# PWR_CTRL.net
KiCad netlist of a schematic drawn in Altium Designer
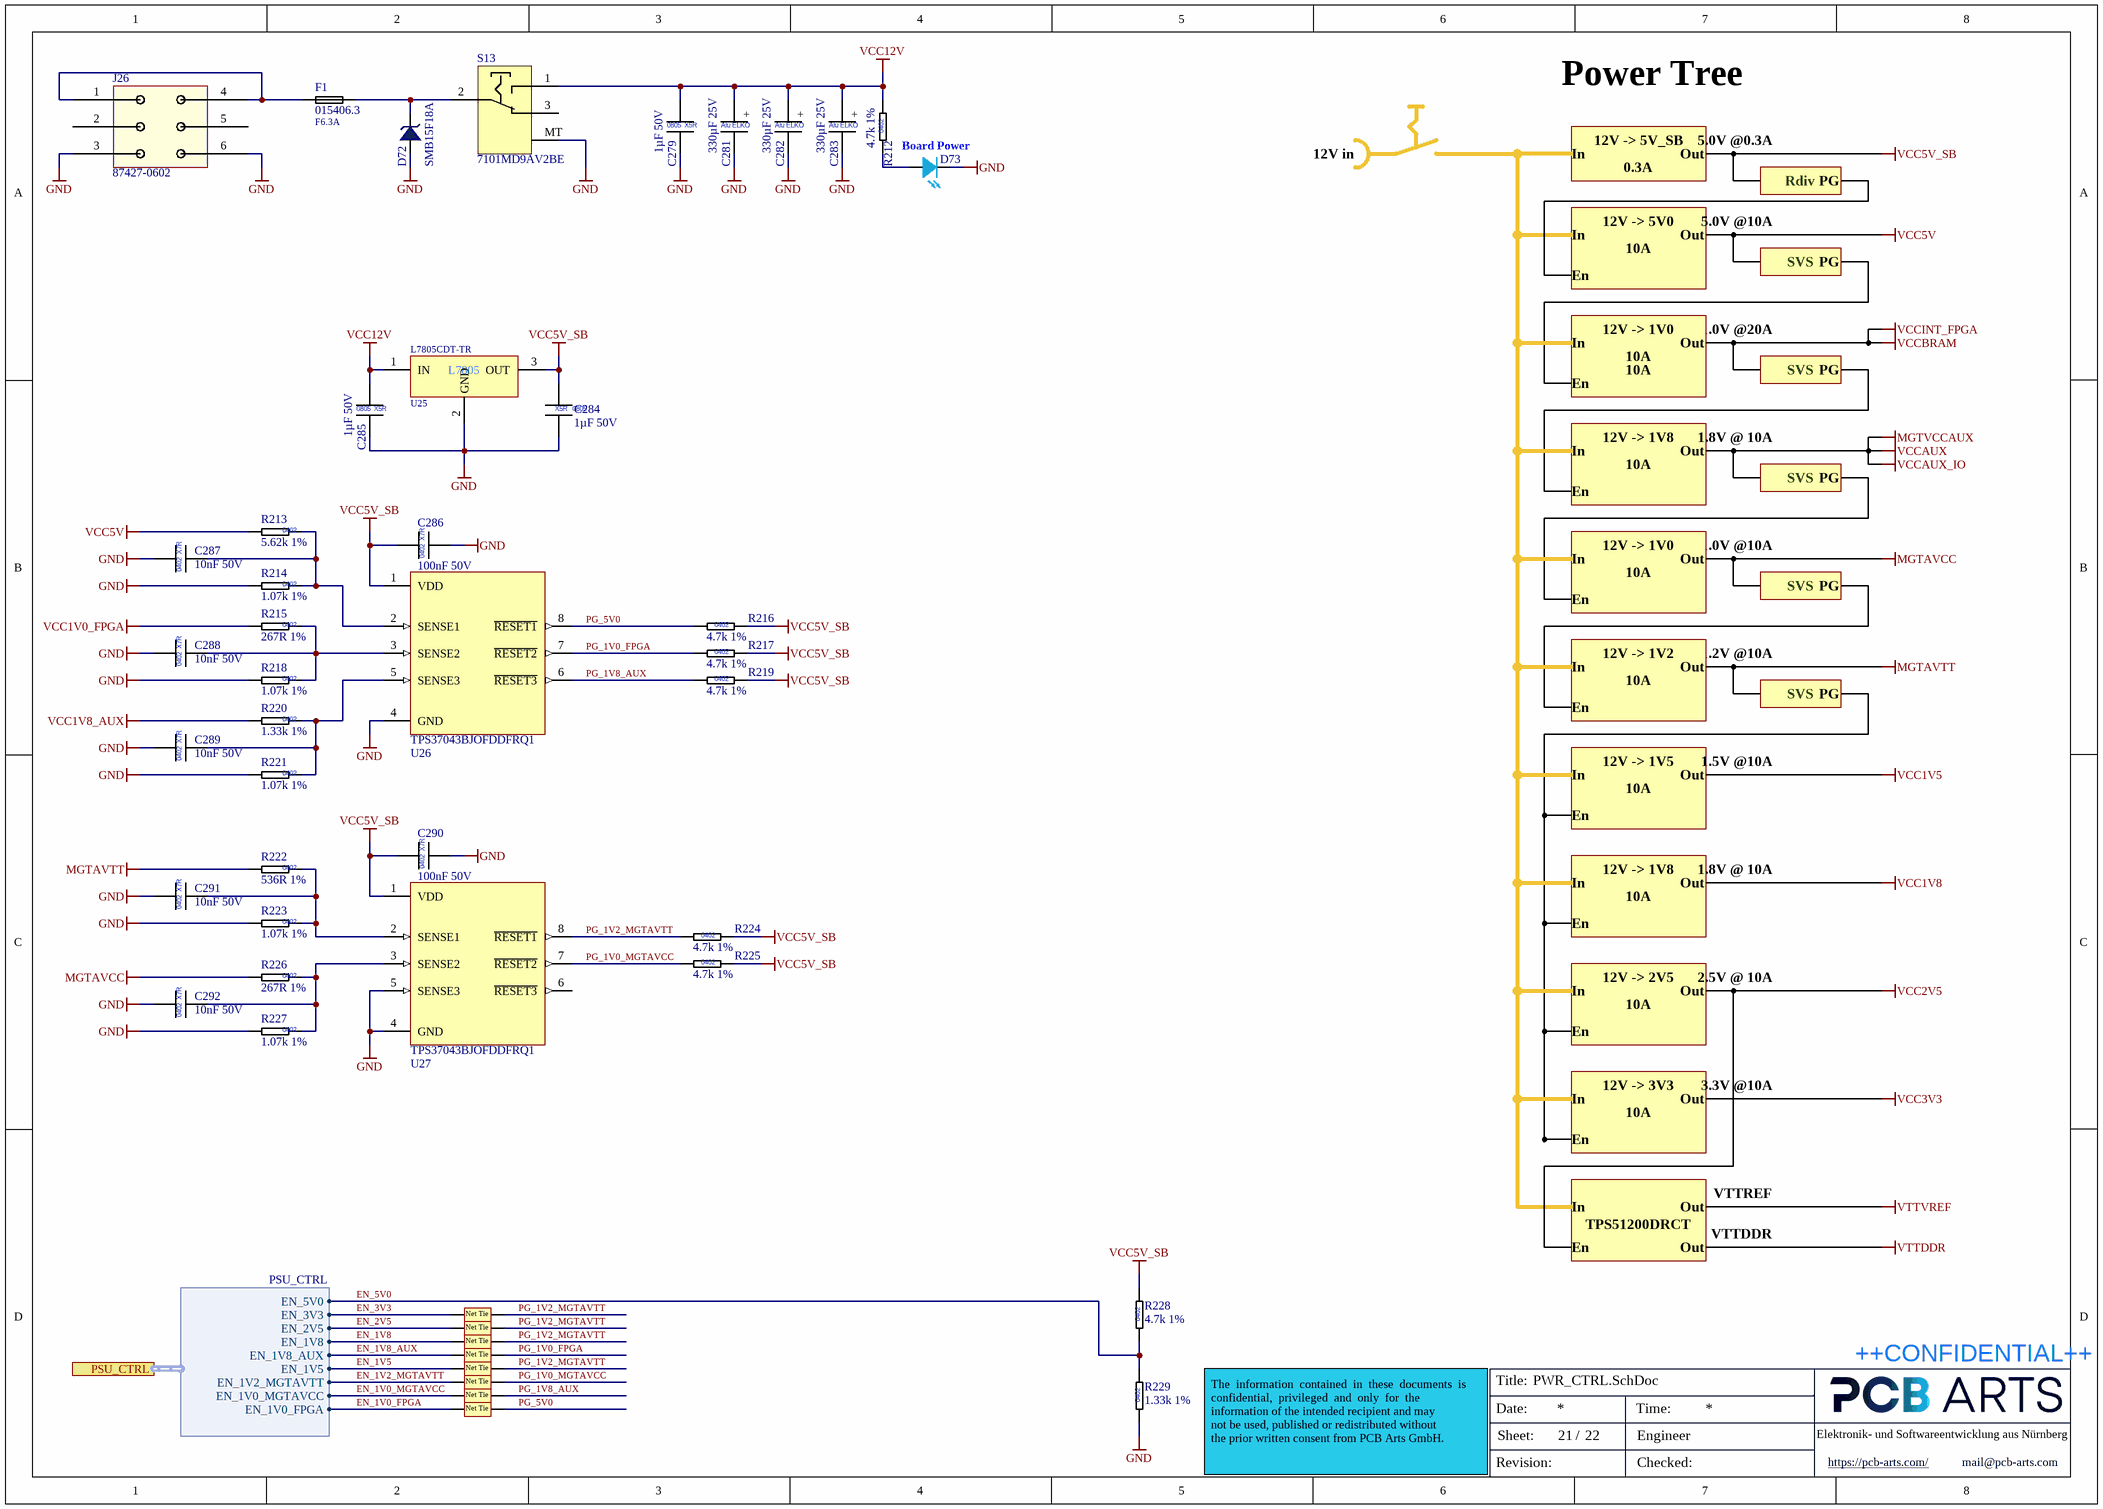
[diagram p0: PWR_CTRL.SchDoc]

(export (version "E")
  (design (tool "Eeschema 10.0.6"))
  (components
    (comp (ref "C279")
      (value "1µF 50V")
      (footprint "Cap:CAP_0805")
      (description "Multilayer Ceramic Capacitors MLCC - SMD/SMT 0805 50VDC")
      (libsource (lib "Cap") (part "CAP_0805_1µF_50V"))
    )
    (comp (ref "C281")
      (value "330µF 25V")
      (footprint "Cap:WCAP-PTG5_D10H12.5")
      (description "Organische Polymer-Aluminiumkondensatoren 330uF 25 Volts 20% AEC-Q200")
      (libsource (lib "Cap") (part "CAP_D10L12.5_330µF_25V"))
    )
    (comp (ref "C282")
      (value "330µF 25V")
      (footprint "Cap:WCAP-PTG5_D10H12.5")
      (description "Organische Polymer-Aluminiumkondensatoren 330uF 25 Volts 20% AEC-Q200")
      (libsource (lib "Cap") (part "CAP_D10L12.5_330µF_25V"))
    )
    (comp (ref "C283")
      (value "330µF 25V")
      (footprint "Cap:WCAP-PTG5_D10H12.5")
      (description "Organische Polymer-Aluminiumkondensatoren 330uF 25 Volts 20% AEC-Q200")
      (libsource (lib "Cap") (part "CAP_D10L12.5_330µF_25V"))
    )
    (comp (ref "C284")
      (value "1µF 50V")
      (footprint "Cap:CAP_0805")
      (description "Multilayer Ceramic Capacitors MLCC - SMD/SMT 0805 50VDC")
      (libsource (lib "Cap") (part "CAP_0805_1µF_50V"))
    )
    (comp (ref "C285")
      (value "1µF 50V")
      (footprint "Cap:CAP_0805")
      (description "Multilayer Ceramic Capacitors MLCC - SMD/SMT 0805 50VDC")
      (libsource (lib "Cap") (part "CAP_0805_1µF_50V"))
    )
    (comp (ref "C286")
      (value "100nF 50V")
      (footprint "Cap:CAP_0402_L")
      (description "Multilayer Ceramic Capacitors MLCC - SMD/SMT 0402 50VDC")
      (libsource (lib "Cap") (part "CAP_0402_100nF_50V"))
    )
    (comp (ref "C287")
      (value "10nF 50V")
      (footprint "Cap:CAP_0402_L")
      (description "Multilayer Ceramic Capacitors MLCC - SMD/SMT 0402 50VDC")
      (libsource (lib "Cap") (part "CAP_0402_10nF_50V"))
    )
    (comp (ref "C288")
      (value "10nF 50V")
      (footprint "Cap:CAP_0402_L")
      (description "Multilayer Ceramic Capacitors MLCC - SMD/SMT 0402 50VDC")
      (libsource (lib "Cap") (part "CAP_0402_10nF_50V"))
    )
    (comp (ref "C289")
      (value "10nF 50V")
      (footprint "Cap:CAP_0402_L")
      (description "Multilayer Ceramic Capacitors MLCC - SMD/SMT 0402 50VDC")
      (libsource (lib "Cap") (part "CAP_0402_10nF_50V"))
    )
    (comp (ref "C290")
      (value "100nF 50V")
      (footprint "Cap:CAP_0402_L")
      (description "Multilayer Ceramic Capacitors MLCC - SMD/SMT 0402 50VDC")
      (libsource (lib "Cap") (part "CAP_0402_100nF_50V"))
    )
    (comp (ref "C291")
      (value "10nF 50V")
      (footprint "Cap:CAP_0402_L")
      (description "Multilayer Ceramic Capacitors MLCC - SMD/SMT 0402 50VDC")
      (libsource (lib "Cap") (part "CAP_0402_10nF_50V"))
    )
    (comp (ref "C292")
      (value "10nF 50V")
      (footprint "Cap:CAP_0402_L")
      (description "Multilayer Ceramic Capacitors MLCC - SMD/SMT 0402 50VDC")
      (libsource (lib "Cap") (part "CAP_0402_10nF_50V"))
    )
    (comp (ref "D72")
      (value "SMB15F18A")
      (footprint "Protec:DO221-AA")
      (description "ESD-Entstörer/TVS-Dioden 1500 W, 18 V TVS")
      (libsource (lib "Protec") (part "SMB15F18A_ESD-Entstörer/TVS-Dioden 1500 W, 18 V TVS"))
    )
    (comp (ref "D73")
      (value "LTST-S270TBKT")
      (footprint "Active:LED-0603 Sideview")
      (description "BLUE  0603 Light Emitting Diode")
      (libsource (lib "Active") (part "LED 0603 Blue Sideview"))
    )
    (comp (ref "F1")
      (value "015406.3")
      (footprint "Passive:154 Series Littelfuse")
      (description "SMD Ceramic Holder with Fuse - Fast 6.3A")
      (fields (field (name "CURRENT") "F6.3A"))
      (libsource (lib "Passive") (part "015406.3_SMD Ceramic Holder with Fuse - Fast 6.3A"))
    )
    (comp (ref "J26")
      (value "87427-0602")
      (footprint "Molex 87427-0602")
      (description "Mini-Fit Jr. Right angle Header, 4.20mm Pitch, Dual Row, 6 Circuits")
      (libsource (lib "Conn") (part "87427-0602_Mini-Fit Jr. Right angle Header, 4.20mm Pitch, Dual Row, 6 Circuits"))
    )
    (comp (ref "NT1")
      (value "Net Tie")
      (footprint "Passive:Net Tie-0.3")
      (libsource (lib "Passive") (part "Net Tie"))
    )
    (comp (ref "NT2")
      (value "Net Tie")
      (footprint "Passive:Net Tie-0.3")
      (libsource (lib "Passive") (part "Net Tie"))
    )
    (comp (ref "NT3")
      (value "Net Tie")
      (footprint "Passive:Net Tie-0.3")
      (libsource (lib "Passive") (part "Net Tie"))
    )
    (comp (ref "NT4")
      (value "Net Tie")
      (footprint "Passive:Net Tie-0.3")
      (libsource (lib "Passive") (part "Net Tie"))
    )
    (comp (ref "NT5")
      (value "Net Tie")
      (footprint "Passive:Net Tie-0.3")
      (libsource (lib "Passive") (part "Net Tie"))
    )
    (comp (ref "NT6")
      (value "Net Tie")
      (footprint "Passive:Net Tie-0.3")
      (libsource (lib "Passive") (part "Net Tie"))
    )
    (comp (ref "NT7")
      (value "Net Tie")
      (footprint "Passive:Net Tie-0.3")
      (libsource (lib "Passive") (part "Net Tie"))
    )
    (comp (ref "NT8")
      (value "Net Tie")
      (footprint "Passive:Net Tie-0.3")
      (libsource (lib "Passive") (part "Net Tie"))
    )
    (comp (ref "R212")
      (value "4.7k 1%")
      (footprint "Res:RES_0402_L")
      (description "Thick Film Resistors - SMD 4.7kOhm 1%")
      (libsource (lib "Res") (part "RES_0402_4.7k_1%"))
    )
    (comp (ref "R213")
      (value "5.62k 1%")
      (footprint "Res:RES_0402_L")
      (description "Thick Film Resistors - SMD 5.62kOhm 1%")
      (libsource (lib "Res") (part "RES_0402_5.62k_1%"))
    )
    (comp (ref "R214")
      (value "1.07k 1%")
      (footprint "Res:RES_0402_L")
      (description "Thick Film Resistors - SMD 1.07kOhm 1%")
      (libsource (lib "Res") (part "RES_0402_1.07k_1%"))
    )
    (comp (ref "R215")
      (value "267R 1%")
      (footprint "Res:RES_0402_L")
      (description "Thick Film Resistors - SMD 267Ohm 1%")
      (libsource (lib "Res") (part "RES_0402_267R_1%"))
    )
    (comp (ref "R216")
      (value "4.7k 1%")
      (footprint "Res:RES_0402_L")
      (description "Thick Film Resistors - SMD 4.7kOhm 1%")
      (libsource (lib "Res") (part "RES_0402_4.7k_1%"))
    )
    (comp (ref "R217")
      (value "4.7k 1%")
      (footprint "Res:RES_0402_L")
      (description "Thick Film Resistors - SMD 4.7kOhm 1%")
      (libsource (lib "Res") (part "RES_0402_4.7k_1%"))
    )
    (comp (ref "R218")
      (value "1.07k 1%")
      (footprint "Res:RES_0402_L")
      (description "Thick Film Resistors - SMD 1.07kOhm 1%")
      (libsource (lib "Res") (part "RES_0402_1.07k_1%"))
    )
    (comp (ref "R219")
      (value "4.7k 1%")
      (footprint "Res:RES_0402_L")
      (description "Thick Film Resistors - SMD 4.7kOhm 1%")
      (libsource (lib "Res") (part "RES_0402_4.7k_1%"))
    )
    (comp (ref "R220")
      (value "1.33k 1%")
      (footprint "Res:RES_0402_L")
      (description "Thick Film Resistors - SMD 1.33kOhm 1%")
      (libsource (lib "Res") (part "RES_0402_1.33k_1%"))
    )
    (comp (ref "R221")
      (value "1.07k 1%")
      (footprint "Res:RES_0402_L")
      (description "Thick Film Resistors - SMD 1.07kOhm 1%")
      (libsource (lib "Res") (part "RES_0402_1.07k_1%"))
    )
    (comp (ref "R222")
      (value "536R 1%")
      (footprint "Res:RES_0402_L")
      (description "Thick Film Resistors - SMD 536Ohm 1%")
      (libsource (lib "Res") (part "RES_0402_536R_1%"))
    )
    (comp (ref "R223")
      (value "1.07k 1%")
      (footprint "Res:RES_0402_L")
      (description "Thick Film Resistors - SMD 1.07kOhm 1%")
      (libsource (lib "Res") (part "RES_0402_1.07k_1%"))
    )
    (comp (ref "R224")
      (value "4.7k 1%")
      (footprint "Res:RES_0402_L")
      (description "Thick Film Resistors - SMD 4.7kOhm 1%")
      (libsource (lib "Res") (part "RES_0402_4.7k_1%"))
    )
    (comp (ref "R225")
      (value "4.7k 1%")
      (footprint "Res:RES_0402_L")
      (description "Thick Film Resistors - SMD 4.7kOhm 1%")
      (libsource (lib "Res") (part "RES_0402_4.7k_1%"))
    )
    (comp (ref "R226")
      (value "267R 1%")
      (footprint "Res:RES_0402_L")
      (description "Thick Film Resistors - SMD 267Ohm 1%")
      (libsource (lib "Res") (part "RES_0402_267R_1%"))
    )
    (comp (ref "R227")
      (value "1.07k 1%")
      (footprint "Res:RES_0402_L")
      (description "Thick Film Resistors - SMD 1.07kOhm 1%")
      (libsource (lib "Res") (part "RES_0402_1.07k_1%"))
    )
    (comp (ref "R228")
      (value "4.7k 1%")
      (footprint "Res:RES_0402_L")
      (description "Thick Film Resistors - SMD 4.7kOhm 1%")
      (libsource (lib "Res") (part "RES_0402_4.7k_1%"))
    )
    (comp (ref "R229")
      (value "1.33k 1%")
      (footprint "Res:RES_0402_L")
      (description "Thick Film Resistors - SMD 1.33kOhm 1%")
      (libsource (lib "Res") (part "RES_0402_1.33k_1%"))
    )
    (comp (ref "S13")
      (value "7101MD9AV2BE")
      (footprint "Electro_Mech:7101MD9AV2BE")
      (description "Kippschalter SPDT Right Angle Vertical")
      (libsource (lib "Electro_Mech") (part "7101MD9AV2BE_Kippschalter SPDT Right Angle Vertical"))
    )
    (comp (ref "U25")
      (value "L7805CDT-TR")
      (footprint "Power:DPAK230P991X241-3N")
      (description "Linear Voltage Regulators 5.0V 1.0A Positive")
      (libsource (lib "Power") (part "L7805CDT-TR_Linear Voltage Regulators 5.0V 1.0A"))
    )
    (comp (ref "U26")
      (value "TPS37043BJOFDDFRQ1")
      (footprint "Comp:SOT65P295X160-8N")
      (description "Triple Supply Voltage Window Supervisors With Fixed Delay, Open Drain Output")
      (libsource (lib "Comp") (part "TPS37043BJOFDDFRQ1_Triple Supply Voltage Window Supervisors"))
    )
    (comp (ref "U27")
      (value "TPS37043BJOFDDFRQ1")
      (footprint "Comp:SOT65P295X160-8N")
      (description "Triple Supply Voltage Window Supervisors With Fixed Delay, Open Drain Output")
      (libsource (lib "Comp") (part "TPS37043BJOFDDFRQ1_Triple Supply Voltage Window Supervisors"))
    )
  )
  (nets
    (net (code "2") (name "/EN_1V0_FPGA") (class "Default")
      (node (ref "NT8") (pin "1") (pinfunction "1_1") (pintype "passive"))
    )
    (net (code "3") (name "/EN_1V0_MGTAVCC") (class "Default")
      (node (ref "NT7") (pin "1") (pinfunction "1_1") (pintype "passive"))
    )
    (net (code "4") (name "/EN_1V2_MGTAVTT") (class "Default")
      (node (ref "NT6") (pin "1") (pinfunction "1_1") (pintype "passive"))
    )
    (net (code "5") (name "/EN_1V5") (class "Default")
      (node (ref "NT5") (pin "1") (pinfunction "1_1") (pintype "passive"))
    )
    (net (code "6") (name "/EN_1V8") (class "Default")
      (node (ref "NT3") (pin "1") (pinfunction "1_1") (pintype "passive"))
    )
    (net (code "7") (name "/EN_1V8_AUX") (class "Default")
      (node (ref "NT4") (pin "1") (pinfunction "1_1") (pintype "passive"))
    )
    (net (code "8") (name "/EN_2V5") (class "Default")
      (node (ref "NT2") (pin "1") (pinfunction "1_1") (pintype "passive"))
    )
    (net (code "9") (name "/EN_3V3") (class "Default")
      (node (ref "NT1") (pin "1") (pinfunction "1_1") (pintype "passive"))
    )
    (net (code "10") (name "/EN_5V0") (class "Default")
      (node (ref "R228") (pin "1") (pinfunction "1_1") (pintype "passive"))
      (node (ref "R229") (pin "2") (pinfunction "2_2") (pintype "passive"))
    )
    (net (code "11") (name "/PG_1V0_FPGA") (class "Default")
      (node (ref "NT4") (pin "2") (pinfunction "2_2") (pintype "passive"))
      (node (ref "R217") (pin "1") (pinfunction "1_1") (pintype "passive"))
      (node (ref "U26") (pin "7") (pinfunction "~{RESET2}_7") (pintype "output"))
    )
    (net (code "12") (name "/PG_1V0_MGTAVCC") (class "Default")
      (node (ref "NT6") (pin "2") (pinfunction "2_2") (pintype "passive"))
      (node (ref "R225") (pin "1") (pinfunction "1_1") (pintype "passive"))
      (node (ref "U27") (pin "7") (pinfunction "~{RESET2}_7") (pintype "output"))
    )
    (net (code "13") (name "/PG_1V2_MGTAVTT") (class "Default")
      (node (ref "NT1") (pin "2") (pinfunction "2_2") (pintype "passive"))
      (node (ref "NT2") (pin "2") (pinfunction "2_2") (pintype "passive"))
      (node (ref "NT3") (pin "2") (pinfunction "2_2") (pintype "passive"))
      (node (ref "NT5") (pin "2") (pinfunction "2_2") (pintype "passive"))
      (node (ref "R224") (pin "1") (pinfunction "1_1") (pintype "passive"))
      (node (ref "U27") (pin "8") (pinfunction "~{RESET1}_8") (pintype "output"))
    )
    (net (code "14") (name "/PG_1V8_AUX") (class "Default")
      (node (ref "NT7") (pin "2") (pinfunction "2_2") (pintype "passive"))
      (node (ref "R219") (pin "1") (pinfunction "1_1") (pintype "passive"))
      (node (ref "U26") (pin "6") (pinfunction "~{RESET3}_6") (pintype "output"))
    )
    (net (code "15") (name "/PG_5V0") (class "Default")
      (node (ref "NT8") (pin "2") (pinfunction "2_2") (pintype "passive"))
      (node (ref "R216") (pin "1") (pinfunction "1_1") (pintype "passive"))
      (node (ref "U26") (pin "8") (pinfunction "~{RESET1}_8") (pintype "output"))
    )
    (net (code "17") (name "GND") (class "Default")
      (node (ref "C279") (pin "2") (pinfunction "2_2") (pintype "passive"))
      (node (ref "C281") (pin "2") (pinfunction "2_2") (pintype "passive"))
      (node (ref "C282") (pin "2") (pinfunction "2_2") (pintype "passive"))
      (node (ref "C283") (pin "2") (pinfunction "2_2") (pintype "passive"))
      (node (ref "C284") (pin "2") (pinfunction "2_2") (pintype "passive"))
      (node (ref "C285") (pin "2") (pinfunction "2_2") (pintype "passive"))
      (node (ref "C286") (pin "2") (pinfunction "2_2") (pintype "passive"))
      (node (ref "C287") (pin "1") (pinfunction "1_1") (pintype "passive"))
      (node (ref "C288") (pin "1") (pinfunction "1_1") (pintype "passive"))
      (node (ref "C289") (pin "1") (pinfunction "1_1") (pintype "passive"))
      (node (ref "C290") (pin "2") (pinfunction "2_2") (pintype "passive"))
      (node (ref "C291") (pin "1") (pinfunction "1_1") (pintype "passive"))
      (node (ref "C292") (pin "1") (pinfunction "1_1") (pintype "passive"))
      (node (ref "D72") (pin "2") (pinfunction "2_2") (pintype "passive"))
      (node (ref "D73") (pin "1") (pinfunction "1_1") (pintype "passive"))
      (node (ref "J26") (pin "3") (pinfunction "3_3") (pintype "passive"))
      (node (ref "J26") (pin "6") (pinfunction "6_6") (pintype "passive"))
      (node (ref "R214") (pin "2") (pinfunction "2_2") (pintype "passive"))
      (node (ref "R218") (pin "2") (pinfunction "2_2") (pintype "passive"))
      (node (ref "R221") (pin "2") (pinfunction "2_2") (pintype "passive"))
      (node (ref "R223") (pin "2") (pinfunction "2_2") (pintype "passive"))
      (node (ref "R227") (pin "2") (pinfunction "2_2") (pintype "passive"))
      (node (ref "R229") (pin "1") (pinfunction "1_1") (pintype "passive"))
      (node (ref "S13") (pin "MT") (pinfunction "2_MT") (pintype "passive"))
      (node (ref "U25") (pin "2") (pinfunction "GND_2") (pintype "passive"))
      (node (ref "U26") (pin "4") (pinfunction "GND_4") (pintype "power_in"))
      (node (ref "U27") (pin "4") (pinfunction "GND_4") (pintype "power_in"))
      (node (ref "U27") (pin "5") (pinfunction "SENSE3_5") (pintype "input"))
    )
    (net (code "18") (name "MGTAVCC") (class "Default")
      (node (ref "R226") (pin "2") (pinfunction "2_2") (pintype "passive"))
    )
    (net (code "19") (name "MGTAVTT") (class "Default")
      (node (ref "R222") (pin "2") (pinfunction "2_2") (pintype "passive"))
    )
    (net (code "21") (name "Net-(D72-Pad1)") (class "Default")
      (node (ref "D72") (pin "1") (pinfunction "1_1") (pintype "passive"))
      (node (ref "F1") (pin "2") (pinfunction "2_2") (pintype "passive"))
      (node (ref "S13") (pin "2") (pinfunction "2_2") (pintype "passive"))
    )
    (net (code "22") (name "Net-(D73-Pad2)") (class "Default")
      (node (ref "D73") (pin "2") (pinfunction "2_2") (pintype "passive"))
      (node (ref "R212") (pin "1") (pinfunction "1_1") (pintype "passive"))
    )
    (net (code "23") (name "Net-(F1-Pad1)") (class "Default")
      (node (ref "F1") (pin "1") (pinfunction "1_1") (pintype "passive"))
      (node (ref "J26") (pin "1") (pinfunction "1_1") (pintype "passive"))
      (node (ref "J26") (pin "4") (pinfunction "4_4") (pintype "passive"))
    )
    (net (code "24") (name "Net-(U26-SENSE1)") (class "Default")
      (node (ref "C287") (pin "2") (pinfunction "2_2") (pintype "passive"))
      (node (ref "R213") (pin "1") (pinfunction "1_1") (pintype "passive"))
      (node (ref "R214") (pin "1") (pinfunction "1_1") (pintype "passive"))
      (node (ref "U26") (pin "2") (pinfunction "SENSE1_2") (pintype "input"))
    )
    (net (code "25") (name "Net-(U26-SENSE2)") (class "Default")
      (node (ref "C288") (pin "2") (pinfunction "2_2") (pintype "passive"))
      (node (ref "R215") (pin "1") (pinfunction "1_1") (pintype "passive"))
      (node (ref "R218") (pin "1") (pinfunction "1_1") (pintype "passive"))
      (node (ref "U26") (pin "3") (pinfunction "SENSE2_3") (pintype "input"))
    )
    (net (code "26") (name "Net-(U26-SENSE3)") (class "Default")
      (node (ref "C289") (pin "2") (pinfunction "2_2") (pintype "passive"))
      (node (ref "R220") (pin "1") (pinfunction "1_1") (pintype "passive"))
      (node (ref "R221") (pin "1") (pinfunction "1_1") (pintype "passive"))
      (node (ref "U26") (pin "5") (pinfunction "SENSE3_5") (pintype "input"))
    )
    (net (code "27") (name "Net-(U27-SENSE1)") (class "Default")
      (node (ref "C291") (pin "2") (pinfunction "2_2") (pintype "passive"))
      (node (ref "R222") (pin "1") (pinfunction "1_1") (pintype "passive"))
      (node (ref "R223") (pin "1") (pinfunction "1_1") (pintype "passive"))
      (node (ref "U27") (pin "2") (pinfunction "SENSE1_2") (pintype "input"))
    )
    (net (code "28") (name "Net-(U27-SENSE2)") (class "Default")
      (node (ref "C292") (pin "2") (pinfunction "2_2") (pintype "passive"))
      (node (ref "R226") (pin "1") (pinfunction "1_1") (pintype "passive"))
      (node (ref "R227") (pin "1") (pinfunction "1_1") (pintype "passive"))
      (node (ref "U27") (pin "3") (pinfunction "SENSE2_3") (pintype "input"))
    )
    (net (code "29") (name "VCC1V0_FPGA") (class "Default")
      (node (ref "R215") (pin "2") (pinfunction "2_2") (pintype "passive"))
    )
    (net (code "32") (name "VCC1V8_AUX") (class "Default")
      (node (ref "R220") (pin "2") (pinfunction "2_2") (pintype "passive"))
    )
    (net (code "35") (name "VCC5V") (class "Default")
      (node (ref "R213") (pin "2") (pinfunction "2_2") (pintype "passive"))
    )
    (net (code "36") (name "VCC5V_SB") (class "Default")
      (node (ref "C284") (pin "1") (pinfunction "1_1") (pintype "passive"))
      (node (ref "C286") (pin "1") (pinfunction "1_1") (pintype "passive"))
      (node (ref "C290") (pin "1") (pinfunction "1_1") (pintype "passive"))
      (node (ref "R216") (pin "2") (pinfunction "2_2") (pintype "passive"))
      (node (ref "R217") (pin "2") (pinfunction "2_2") (pintype "passive"))
      (node (ref "R219") (pin "2") (pinfunction "2_2") (pintype "passive"))
      (node (ref "R224") (pin "2") (pinfunction "2_2") (pintype "passive"))
      (node (ref "R225") (pin "2") (pinfunction "2_2") (pintype "passive"))
      (node (ref "R228") (pin "2") (pinfunction "2_2") (pintype "passive"))
      (node (ref "U25") (pin "3") (pinfunction "OUT_3") (pintype "passive"))
      (node (ref "U26") (pin "1") (pinfunction "VDD_1") (pintype "power_in"))
      (node (ref "U27") (pin "1") (pinfunction "VDD_1") (pintype "power_in"))
    )
    (net (code "37") (name "VCC12V") (class "Default")
      (node (ref "C279") (pin "1") (pinfunction "1_1") (pintype "passive"))
      (node (ref "C281") (pin "1") (pinfunction "1_1") (pintype "passive"))
      (node (ref "C282") (pin "1") (pinfunction "1_1") (pintype "passive"))
      (node (ref "C283") (pin "1") (pinfunction "1_1") (pintype "passive"))
      (node (ref "C285") (pin "1") (pinfunction "1_1") (pintype "passive"))
      (node (ref "R212") (pin "2") (pinfunction "2_2") (pintype "passive"))
      (node (ref "S13") (pin "1") (pinfunction "1_1") (pintype "passive"))
      (node (ref "U25") (pin "1") (pinfunction "IN_1") (pintype "passive"))
    )
    (net (code "44") (name "unconnected-(J26-Pad2)") (class "Default")
      (node (ref "J26") (pin "2") (pinfunction "2_2") (pintype "passive"))
    )
    (net (code "45") (name "unconnected-(J26-Pad5)") (class "Default")
      (node (ref "J26") (pin "5") (pinfunction "5_5") (pintype "passive"))
    )
    (net (code "46") (name "unconnected-(S13-Pad3)") (class "Default")
      (node (ref "S13") (pin "3") (pinfunction "3_3") (pintype "passive"))
    )
    (net (code "47") (name "unconnected-(U27-~{RESET3}-Pad6)") (class "Default")
      (node (ref "U27") (pin "6") (pinfunction "~{RESET3}_6") (pintype "output"))
    )
  )
)
